# darlington_array.net
KiCad netlist of a schematic drawn in EAGLE
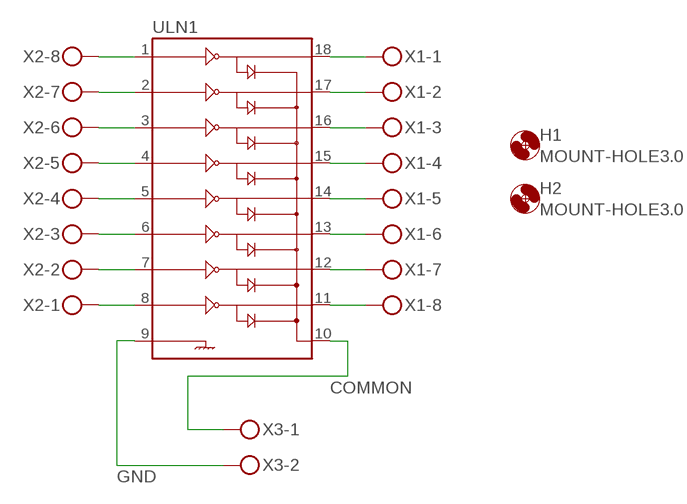
[diagram p0: schematic, sheet 1]

(export (version "E")
  (design (tool "Eeschema 10.0.6"))
  (components
    (comp (ref "H1")
      (value "MOUNT-HOLE3.0")
      (footprint "eagle-import:3,0")
      (libsource (lib "eagle-import") (part "MOUNT-HOLE3.0"))
    )
    (comp (ref "H2")
      (value "MOUNT-HOLE3.0")
      (footprint "eagle-import:3,0")
      (libsource (lib "eagle-import") (part "MOUNT-HOLE3.0"))
    )
    (comp (ref "ULN1")
      (value "ULN2803DIP")
      (footprint "eagle-import:DIL18")
      (libsource (lib "eagle-import") (part "ULN2803DIP"))
    )
    (comp (ref "X1")
      (value "MKDSN1,5/8-5,08")
      (footprint "eagle-import:MKDSN1,5_8-5,08")
      (libsource (lib "eagle-import") (part "MKDSN1,5/8-5,08"))
    )
    (comp (ref "X2")
      (value "MKDSN1,5/8-5,08")
      (footprint "eagle-import:MKDSN1,5_8-5,08")
      (libsource (lib "eagle-import") (part "MKDSN1,5/8-5,08"))
    )
    (comp (ref "X3")
      (value "MKDSN1,5/2-5,08")
      (footprint "eagle-import:MKDSN1,5_2-5,08")
      (libsource (lib "eagle-import") (part "MKDSN1,5/2-5,08"))
    )
  )
  (nets
    (net (code "1") (name "/COMMON") (class "Default")
      (node (ref "ULN1") (pin "10") (pinfunction "10_10") (pintype "bidirectional"))
      (node (ref "X3") (pin "1") (pinfunction "KL_1") (pintype "passive"))
    )
    (net (code "2") (name "/GND") (class "Default")
      (node (ref "ULN1") (pin "9") (pinfunction "9_9") (pintype "bidirectional"))
      (node (ref "X3") (pin "2") (pinfunction "KL_2") (pintype "passive"))
    )
    (net (code "3") (name "Net-(X1A-KL)") (class "Default")
      (node (ref "ULN1") (pin "18") (pinfunction "18_18") (pintype "bidirectional"))
      (node (ref "X1") (pin "1") (pinfunction "KL_1") (pintype "passive"))
    )
    (net (code "4") (name "Net-(X1B-KL)") (class "Default")
      (node (ref "ULN1") (pin "17") (pinfunction "17_17") (pintype "bidirectional"))
      (node (ref "X1") (pin "2") (pinfunction "KL_2") (pintype "passive"))
    )
    (net (code "5") (name "Net-(X1C-KL)") (class "Default")
      (node (ref "ULN1") (pin "16") (pinfunction "16_16") (pintype "bidirectional"))
      (node (ref "X1") (pin "3") (pinfunction "KL_3") (pintype "passive"))
    )
    (net (code "6") (name "Net-(X1D-KL)") (class "Default")
      (node (ref "ULN1") (pin "15") (pinfunction "15_15") (pintype "bidirectional"))
      (node (ref "X1") (pin "4") (pinfunction "KL_4") (pintype "passive"))
    )
    (net (code "7") (name "Net-(X1E-KL)") (class "Default")
      (node (ref "ULN1") (pin "14") (pinfunction "14_14") (pintype "bidirectional"))
      (node (ref "X1") (pin "5") (pinfunction "KL_5") (pintype "passive"))
    )
    (net (code "8") (name "Net-(X1F-KL)") (class "Default")
      (node (ref "ULN1") (pin "13") (pinfunction "13_13") (pintype "bidirectional"))
      (node (ref "X1") (pin "6") (pinfunction "KL_6") (pintype "passive"))
    )
    (net (code "9") (name "Net-(X1G-KL)") (class "Default")
      (node (ref "ULN1") (pin "12") (pinfunction "12_12") (pintype "bidirectional"))
      (node (ref "X1") (pin "7") (pinfunction "KL_7") (pintype "passive"))
    )
    (net (code "10") (name "Net-(X1H-KL)") (class "Default")
      (node (ref "ULN1") (pin "11") (pinfunction "11_11") (pintype "bidirectional"))
      (node (ref "X1") (pin "8") (pinfunction "KL_8") (pintype "passive"))
    )
    (net (code "11") (name "Net-(X2A-KL)") (class "Default")
      (node (ref "ULN1") (pin "8") (pinfunction "8_8") (pintype "bidirectional"))
      (node (ref "X2") (pin "1") (pinfunction "KL_1") (pintype "passive"))
    )
    (net (code "12") (name "Net-(X2B-KL)") (class "Default")
      (node (ref "ULN1") (pin "7") (pinfunction "7_7") (pintype "bidirectional"))
      (node (ref "X2") (pin "2") (pinfunction "KL_2") (pintype "passive"))
    )
    (net (code "13") (name "Net-(X2C-KL)") (class "Default")
      (node (ref "ULN1") (pin "6") (pinfunction "6_6") (pintype "bidirectional"))
      (node (ref "X2") (pin "3") (pinfunction "KL_3") (pintype "passive"))
    )
    (net (code "14") (name "Net-(X2D-KL)") (class "Default")
      (node (ref "ULN1") (pin "5") (pinfunction "5_5") (pintype "bidirectional"))
      (node (ref "X2") (pin "4") (pinfunction "KL_4") (pintype "passive"))
    )
    (net (code "15") (name "Net-(X2E-KL)") (class "Default")
      (node (ref "ULN1") (pin "4") (pinfunction "4_4") (pintype "bidirectional"))
      (node (ref "X2") (pin "5") (pinfunction "KL_5") (pintype "passive"))
    )
    (net (code "16") (name "Net-(X2F-KL)") (class "Default")
      (node (ref "ULN1") (pin "3") (pinfunction "3_3") (pintype "bidirectional"))
      (node (ref "X2") (pin "6") (pinfunction "KL_6") (pintype "passive"))
    )
    (net (code "17") (name "Net-(X2G-KL)") (class "Default")
      (node (ref "ULN1") (pin "2") (pinfunction "2_2") (pintype "bidirectional"))
      (node (ref "X2") (pin "7") (pinfunction "KL_7") (pintype "passive"))
    )
    (net (code "18") (name "Net-(X2H-KL)") (class "Default")
      (node (ref "ULN1") (pin "1") (pinfunction "1_1") (pintype "bidirectional"))
      (node (ref "X2") (pin "8") (pinfunction "KL_8") (pintype "passive"))
    )
  )
)
